# Sheet1.net
KiCad netlist of a schematic drawn in Altium Designer
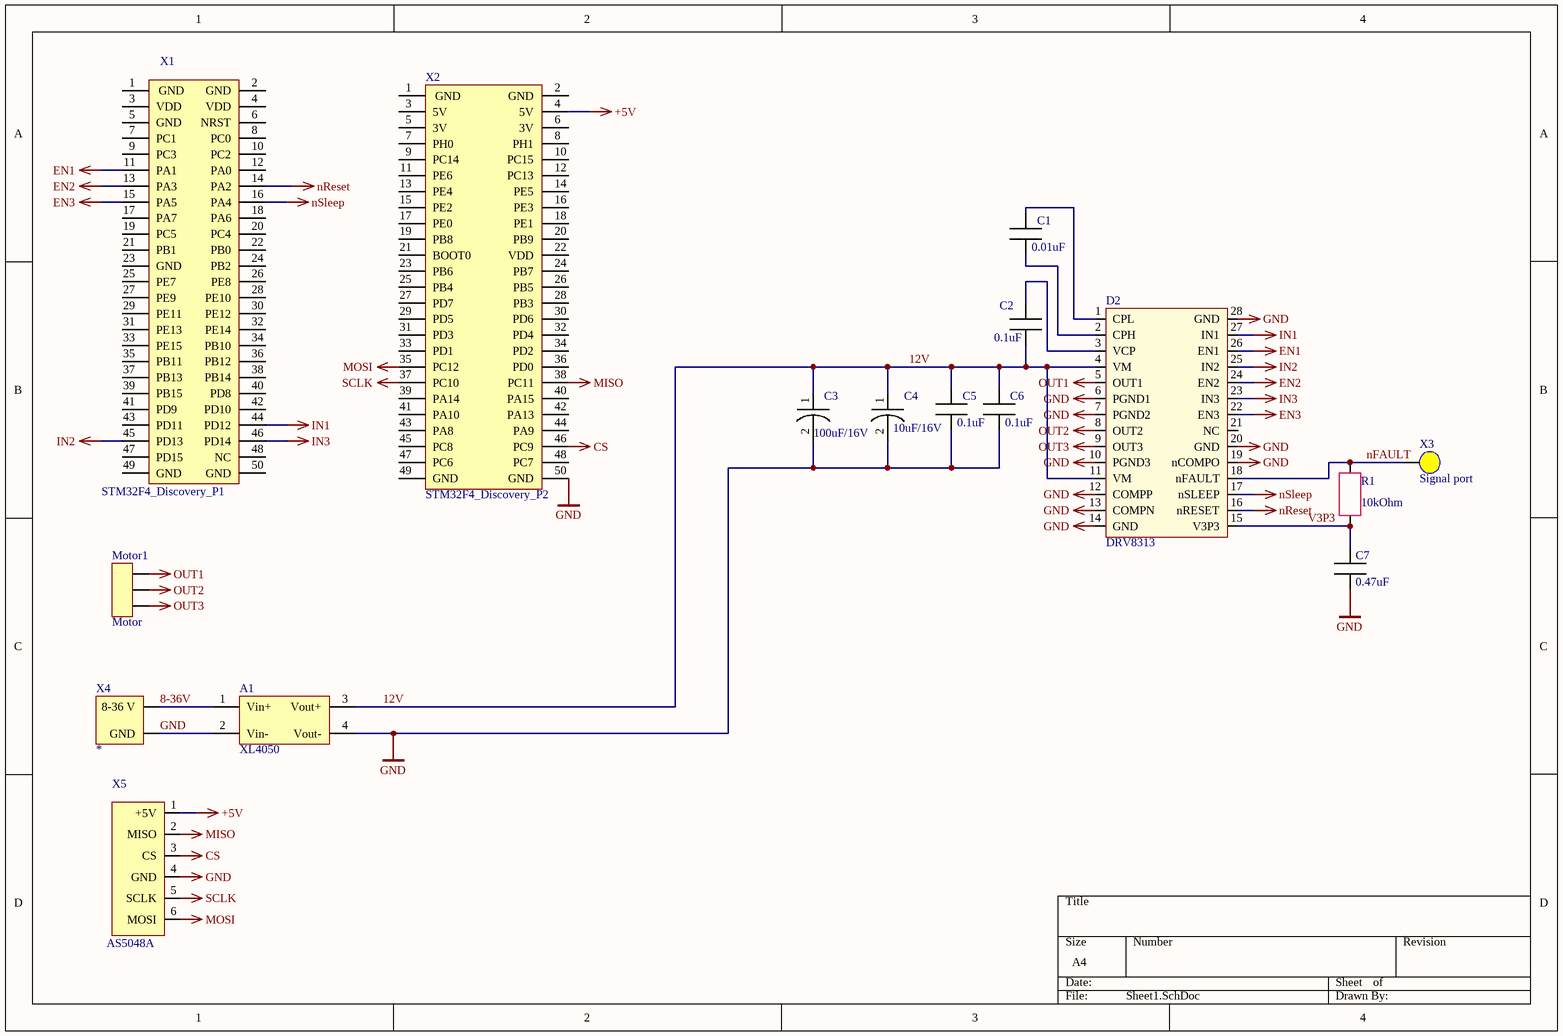
[diagram p0: Sheet1.SchDoc]

(export (version "E")
  (design (tool "Eeschema 10.0.6"))
  (components
    (comp (ref "A1")
      (value "XL4050")
      (footprint "XL4050_PCB")
      (libsource (lib "Schlib1") (part "XL4050_PCB"))
    )
    (comp (ref "C1")
      (value "0.01uF")
      (footprint "Ceramic 1206 - duplicate")
      (libsource (lib "Schlib1") (part "Ceramic capacitor 1206"))
    )
    (comp (ref "C2")
      (value "0.1uF")
      (footprint "Ceramic 1206 - duplicate")
      (libsource (lib "Schlib1") (part "Ceramic capacitor 1206"))
    )
    (comp (ref "C3")
      (value "100uF/16V")
      (footprint "CAP 50-35 5х11")
      (libsource (lib "Schlib1") (part "Elecrolite, К50-35, 100uF/16V"))
    )
    (comp (ref "C4")
      (value "10uF/16V")
      (footprint "CAP 50-35 5х11")
      (libsource (lib "Schlib1") (part "Electrolite, K50-35, 10uF/63V"))
    )
    (comp (ref "C5")
      (value "0.1uF")
      (footprint "Ceramic 1206 - duplicate")
      (libsource (lib "Schlib1") (part "Ceramic capacitor 1206"))
    )
    (comp (ref "C6")
      (value "0.1uF")
      (footprint "Ceramic 1206 - duplicate")
      (libsource (lib "Schlib1") (part "Ceramic capacitor 1206"))
    )
    (comp (ref "C7")
      (value "0.47uF")
      (footprint "Ceramic 1206 - duplicate")
      (libsource (lib "Schlib1") (part "Ceramic capacitor 1206"))
    )
    (comp (ref "D2")
      (value "DRV8313")
      (footprint "PcbLib1:DRV8313 board")
      (libsource (lib "Schlib1") (part "DRV8313"))
    )
    (comp (ref "Motor1")
      (value "Motor")
      (footprint "Fhase out")
      (libsource (lib "Schlib1") (part "Fhase out"))
    )
    (comp (ref "R1")
      (value "10kOhm")
      (footprint "PcbLib1:Resistor 1206")
      (libsource (lib "Schlib1") (part "Resistor"))
    )
    (comp (ref "X1")
      (value "STM32F4_Discovery_P1")
      (footprint "STM32F4Discovery_P")
      (libsource (lib "Schlib1") (part "STM32F4_Discovery_P1"))
    )
    (comp (ref "X2")
      (value "STM32F4_Discovery_P2")
      (footprint "STM32F4Discovery_P")
      (libsource (lib "Schlib1") (part "STM32F4_Discovery_P2"))
    )
    (comp (ref "X3")
      (value "Signal port")
      (footprint "Signal port")
      (libsource (lib "Schlib1") (part "Signal port"))
    )
    (comp (ref "X4") (value "*") (footprint "Power input") (libsource (lib "Schlib1") (part "Power input")))
    (comp (ref "X5")
      (value "AS5048A")
      (footprint "AS5048A_input")
      (libsource (lib "Schlib1") (part "AS5048A_PCB"))
    )
  )
  (nets
    (net (code "1") (name "+5V") (class "Default")
      (node (ref "X2") (pin "4") (pinfunction "5V_4") (pintype "passive"))
      (node (ref "X5") (pin "1") (pinfunction "+5V_1") (pintype "passive"))
    )
    (net (code "2") (name "/8-36V") (class "Default")
      (node (ref "A1") (pin "1") (pinfunction "Vin+_1") (pintype "passive"))
      (node (ref "X4") (pin "1") (pinfunction "8-36_V_1") (pintype "passive"))
    )
    (net (code "3") (name "/12V") (class "Default")
      (node (ref "A1") (pin "3") (pinfunction "Vout+_3") (pintype "passive"))
      (node (ref "C2") (pin "2") (pintype "passive"))
      (node (ref "C3") (pin "1") (pinfunction "+_1") (pintype "passive"))
      (node (ref "C4") (pin "1") (pinfunction "+_1") (pintype "passive"))
      (node (ref "C5") (pin "1") (pintype "passive"))
      (node (ref "C6") (pin "1") (pintype "passive"))
      (node (ref "D2") (pin "11") (pinfunction "VM_11") (pintype "passive"))
      (node (ref "D2") (pin "4") (pinfunction "VM_4") (pintype "passive"))
    )
    (net (code "4") (name "/V3P3") (class "Default")
      (node (ref "C7") (pin "1") (pintype "passive"))
      (node (ref "D2") (pin "15") (pinfunction "V3P3_15") (pintype "passive"))
      (node (ref "R1") (pin "1") (pinfunction "1_1") (pintype "passive"))
    )
    (net (code "5") (name "/nFAULT") (class "Default")
      (node (ref "D2") (pin "18") (pinfunction "nFAULT_18") (pintype "passive"))
      (node (ref "R1") (pin "2") (pinfunction "2_2") (pintype "passive"))
      (node (ref "X3") (pin "1") (pintype "passive"))
    )
    (net (code "6") (name "CS") (class "Default")
      (node (ref "X2") (pin "46") (pinfunction "PC9_46") (pintype "passive"))
      (node (ref "X5") (pin "3") (pinfunction "CS_3") (pintype "passive"))
    )
    (net (code "7") (name "EN1") (class "Default")
      (node (ref "D2") (pin "26") (pinfunction "EN1_26") (pintype "passive"))
      (node (ref "X1") (pin "11") (pinfunction "PA1_11") (pintype "passive"))
    )
    (net (code "8") (name "EN2") (class "Default")
      (node (ref "D2") (pin "24") (pinfunction "EN2_24") (pintype "passive"))
      (node (ref "X1") (pin "13") (pinfunction "PA3_13") (pintype "passive"))
    )
    (net (code "9") (name "EN3") (class "Default")
      (node (ref "D2") (pin "22") (pinfunction "EN3_22") (pintype "passive"))
      (node (ref "X1") (pin "15") (pinfunction "PA5_15") (pintype "passive"))
    )
    (net (code "10") (name "GND") (class "Default")
      (node (ref "A1") (pin "2") (pinfunction "Vin-_2") (pintype "passive"))
      (node (ref "A1") (pin "4") (pinfunction "Vout-_4") (pintype "passive"))
      (node (ref "C3") (pin "2") (pinfunction "-_2") (pintype "passive"))
      (node (ref "C4") (pin "2") (pinfunction "-_2") (pintype "passive"))
      (node (ref "C5") (pin "2") (pintype "passive"))
      (node (ref "C6") (pin "2") (pintype "passive"))
      (node (ref "C7") (pin "2") (pintype "passive"))
      (node (ref "D2") (pin "10") (pinfunction "PGND3_10") (pintype "passive"))
      (node (ref "D2") (pin "12") (pinfunction "COMPP_12") (pintype "passive"))
      (node (ref "D2") (pin "13") (pinfunction "COMPN_13") (pintype "passive"))
      (node (ref "D2") (pin "14") (pinfunction "GND_14") (pintype "passive"))
      (node (ref "D2") (pin "19") (pinfunction "nCOMPO_19") (pintype "passive"))
      (node (ref "D2") (pin "20") (pinfunction "GND_20") (pintype "passive"))
      (node (ref "D2") (pin "28") (pinfunction "GND_28") (pintype "passive"))
      (node (ref "D2") (pin "6") (pinfunction "PGND1_6") (pintype "passive"))
      (node (ref "D2") (pin "7") (pinfunction "PGND2_7") (pintype "passive"))
      (node (ref "X2") (pin "50") (pinfunction "GND_50") (pintype "passive"))
      (node (ref "X4") (pin "2") (pinfunction "GND_2") (pintype "passive"))
      (node (ref "X5") (pin "4") (pinfunction "GND_4") (pintype "passive"))
    )
    (net (code "11") (name "IN1") (class "Default")
      (node (ref "D2") (pin "27") (pinfunction "IN1_27") (pintype "passive"))
      (node (ref "X1") (pin "44") (pinfunction "PD12_44") (pintype "passive"))
    )
    (net (code "12") (name "IN2") (class "Default")
      (node (ref "D2") (pin "25") (pinfunction "IN2_25") (pintype "passive"))
      (node (ref "X1") (pin "45") (pinfunction "PD13_45") (pintype "passive"))
    )
    (net (code "13") (name "IN3") (class "Default")
      (node (ref "D2") (pin "23") (pinfunction "IN3_23") (pintype "passive"))
      (node (ref "X1") (pin "46") (pinfunction "PD14_46") (pintype "passive"))
    )
    (net (code "14") (name "MISO") (class "Default")
      (node (ref "X2") (pin "38") (pinfunction "PC11_38") (pintype "passive"))
      (node (ref "X5") (pin "2") (pinfunction "MISO_2") (pintype "passive"))
    )
    (net (code "15") (name "MOSI") (class "Default")
      (node (ref "X2") (pin "35") (pinfunction "PC12_35") (pintype "passive"))
      (node (ref "X5") (pin "6") (pinfunction "MOSI_6") (pintype "passive"))
    )
    (net (code "16") (name "Net-(D2-CPH)") (class "Default")
      (node (ref "C1") (pin "2") (pintype "passive"))
      (node (ref "D2") (pin "2") (pinfunction "CPH_2") (pintype "passive"))
    )
    (net (code "17") (name "Net-(D2-CPL)") (class "Default")
      (node (ref "C1") (pin "1") (pintype "passive"))
      (node (ref "D2") (pin "1") (pinfunction "CPL_1") (pintype "passive"))
    )
    (net (code "18") (name "Net-(D2-VCP)") (class "Default")
      (node (ref "C2") (pin "1") (pintype "passive"))
      (node (ref "D2") (pin "3") (pinfunction "VCP_3") (pintype "passive"))
    )
    (net (code "19") (name "OUT1") (class "Default")
      (node (ref "D2") (pin "5") (pinfunction "OUT1_5") (pintype "passive"))
      (node (ref "Motor1") (pin "1") (pintype "passive"))
    )
    (net (code "20") (name "OUT2") (class "Default")
      (node (ref "D2") (pin "8") (pinfunction "OUT2_8") (pintype "passive"))
      (node (ref "Motor1") (pin "2") (pintype "passive"))
    )
    (net (code "21") (name "OUT3") (class "Default")
      (node (ref "D2") (pin "9") (pinfunction "OUT3_9") (pintype "passive"))
      (node (ref "Motor1") (pin "3") (pintype "passive"))
    )
    (net (code "22") (name "SCLK") (class "Default")
      (node (ref "X2") (pin "37") (pinfunction "PC10_37") (pintype "passive"))
      (node (ref "X5") (pin "5") (pinfunction "SCLK_5") (pintype "passive"))
    )
    (net (code "23") (name "nReset") (class "Default")
      (node (ref "D2") (pin "16") (pinfunction "nRESET_16") (pintype "passive"))
      (node (ref "X1") (pin "14") (pinfunction "PA2_14") (pintype "passive"))
    )
    (net (code "24") (name "nSleep") (class "Default")
      (node (ref "D2") (pin "17") (pinfunction "nSLEEP_17") (pintype "passive"))
      (node (ref "X1") (pin "16") (pinfunction "PA4_16") (pintype "passive"))
    )
    (net (code "25") (name "unconnected-(D2-NC-Pad21)") (class "Default")
      (node (ref "D2") (pin "21") (pinfunction "NC_21") (pintype "passive"))
    )
    (net (code "26") (name "unconnected-(X1-GND-Pad1)") (class "Default")
      (node (ref "X1") (pin "1") (pinfunction "GND_1") (pintype "passive"))
    )
    (net (code "27") (name "unconnected-(X1-GND-Pad2)") (class "Default")
      (node (ref "X1") (pin "2") (pinfunction "GND_2") (pintype "passive"))
    )
    (net (code "28") (name "unconnected-(X1-GND-Pad5)") (class "Default")
      (node (ref "X1") (pin "5") (pinfunction "GND_5") (pintype "passive"))
    )
    (net (code "29") (name "unconnected-(X1-GND-Pad23)") (class "Default")
      (node (ref "X1") (pin "23") (pinfunction "GND_23") (pintype "passive"))
    )
    (net (code "30") (name "unconnected-(X1-GND-Pad49)") (class "Default")
      (node (ref "X1") (pin "49") (pinfunction "GND_49") (pintype "passive"))
    )
    (net (code "31") (name "unconnected-(X1-GND-Pad50)") (class "Default")
      (node (ref "X1") (pin "50") (pinfunction "GND_50") (pintype "passive"))
    )
    (net (code "32") (name "unconnected-(X1-NC-Pad48)") (class "Default")
      (node (ref "X1") (pin "48") (pinfunction "NC_48") (pintype "passive"))
    )
    (net (code "33") (name "unconnected-(X1-NRST-Pad6)") (class "Default")
      (node (ref "X1") (pin "6") (pinfunction "NRST_6") (pintype "passive"))
    )
    (net (code "34") (name "unconnected-(X1-PA0-Pad12)") (class "Default")
      (node (ref "X1") (pin "12") (pinfunction "PA0_12") (pintype "passive"))
    )
    (net (code "35") (name "unconnected-(X1-PA6-Pad18)") (class "Default")
      (node (ref "X1") (pin "18") (pinfunction "PA6_18") (pintype "passive"))
    )
    (net (code "36") (name "unconnected-(X1-PA7-Pad17)") (class "Default")
      (node (ref "X1") (pin "17") (pinfunction "PA7_17") (pintype "passive"))
    )
    (net (code "37") (name "unconnected-(X1-PB0-Pad22)") (class "Default")
      (node (ref "X1") (pin "22") (pinfunction "PB0_22") (pintype "passive"))
    )
    (net (code "38") (name "unconnected-(X1-PB1-Pad21)") (class "Default")
      (node (ref "X1") (pin "21") (pinfunction "PB1_21") (pintype "passive"))
    )
    (net (code "39") (name "unconnected-(X1-PB2-Pad24)") (class "Default")
      (node (ref "X1") (pin "24") (pinfunction "PB2_24") (pintype "passive"))
    )
    (net (code "40") (name "unconnected-(X1-PB10-Pad34)") (class "Default")
      (node (ref "X1") (pin "34") (pinfunction "PB10_34") (pintype "passive"))
    )
    (net (code "41") (name "unconnected-(X1-PB11-Pad35)") (class "Default")
      (node (ref "X1") (pin "35") (pinfunction "PB11_35") (pintype "passive"))
    )
    (net (code "42") (name "unconnected-(X1-PB12-Pad36)") (class "Default")
      (node (ref "X1") (pin "36") (pinfunction "PB12_36") (pintype "passive"))
    )
    (net (code "43") (name "unconnected-(X1-PB13-Pad37)") (class "Default")
      (node (ref "X1") (pin "37") (pinfunction "PB13_37") (pintype "passive"))
    )
    (net (code "44") (name "unconnected-(X1-PB14-Pad38)") (class "Default")
      (node (ref "X1") (pin "38") (pinfunction "PB14_38") (pintype "passive"))
    )
    (net (code "45") (name "unconnected-(X1-PB15-Pad39)") (class "Default")
      (node (ref "X1") (pin "39") (pinfunction "PB15_39") (pintype "passive"))
    )
    (net (code "46") (name "unconnected-(X1-PC0-Pad8)") (class "Default")
      (node (ref "X1") (pin "8") (pinfunction "PC0_8") (pintype "passive"))
    )
    (net (code "47") (name "unconnected-(X1-PC1-Pad7)") (class "Default")
      (node (ref "X1") (pin "7") (pinfunction "PC1_7") (pintype "passive"))
    )
    (net (code "48") (name "unconnected-(X1-PC2-Pad10)") (class "Default")
      (node (ref "X1") (pin "10") (pinfunction "PC2_10") (pintype "passive"))
    )
    (net (code "49") (name "unconnected-(X1-PC3-Pad9)") (class "Default")
      (node (ref "X1") (pin "9") (pinfunction "PC3_9") (pintype "passive"))
    )
    (net (code "50") (name "unconnected-(X1-PC4-Pad20)") (class "Default")
      (node (ref "X1") (pin "20") (pinfunction "PC4_20") (pintype "passive"))
    )
    (net (code "51") (name "unconnected-(X1-PC5-Pad19)") (class "Default")
      (node (ref "X1") (pin "19") (pinfunction "PC5_19") (pintype "passive"))
    )
    (net (code "52") (name "unconnected-(X1-PD8-Pad40)") (class "Default")
      (node (ref "X1") (pin "40") (pinfunction "PD8_40") (pintype "passive"))
    )
    (net (code "53") (name "unconnected-(X1-PD9-Pad41)") (class "Default")
      (node (ref "X1") (pin "41") (pinfunction "PD9_41") (pintype "passive"))
    )
    (net (code "54") (name "unconnected-(X1-PD10-Pad42)") (class "Default")
      (node (ref "X1") (pin "42") (pinfunction "PD10_42") (pintype "passive"))
    )
    (net (code "55") (name "unconnected-(X1-PD11-Pad43)") (class "Default")
      (node (ref "X1") (pin "43") (pinfunction "PD11_43") (pintype "passive"))
    )
    (net (code "56") (name "unconnected-(X1-PD15-Pad47)") (class "Default")
      (node (ref "X1") (pin "47") (pinfunction "PD15_47") (pintype "passive"))
    )
    (net (code "57") (name "unconnected-(X1-PE7-Pad25)") (class "Default")
      (node (ref "X1") (pin "25") (pinfunction "PE7_25") (pintype "passive"))
    )
    (net (code "58") (name "unconnected-(X1-PE8-Pad26)") (class "Default")
      (node (ref "X1") (pin "26") (pinfunction "PE8_26") (pintype "passive"))
    )
    (net (code "59") (name "unconnected-(X1-PE9-Pad27)") (class "Default")
      (node (ref "X1") (pin "27") (pinfunction "PE9_27") (pintype "passive"))
    )
    (net (code "60") (name "unconnected-(X1-PE10-Pad28)") (class "Default")
      (node (ref "X1") (pin "28") (pinfunction "PE10_28") (pintype "passive"))
    )
    (net (code "61") (name "unconnected-(X1-PE11-Pad29)") (class "Default")
      (node (ref "X1") (pin "29") (pinfunction "PE11_29") (pintype "passive"))
    )
    (net (code "62") (name "unconnected-(X1-PE12-Pad30)") (class "Default")
      (node (ref "X1") (pin "30") (pinfunction "PE12_30") (pintype "passive"))
    )
    (net (code "63") (name "unconnected-(X1-PE13-Pad31)") (class "Default")
      (node (ref "X1") (pin "31") (pinfunction "PE13_31") (pintype "passive"))
    )
    (net (code "64") (name "unconnected-(X1-PE14-Pad32)") (class "Default")
      (node (ref "X1") (pin "32") (pinfunction "PE14_32") (pintype "passive"))
    )
    (net (code "65") (name "unconnected-(X1-PE15-Pad33)") (class "Default")
      (node (ref "X1") (pin "33") (pinfunction "PE15_33") (pintype "passive"))
    )
    (net (code "66") (name "unconnected-(X1-VDD-Pad3)") (class "Default")
      (node (ref "X1") (pin "3") (pinfunction "VDD_3") (pintype "passive"))
    )
    (net (code "67") (name "unconnected-(X1-VDD-Pad4)") (class "Default")
      (node (ref "X1") (pin "4") (pinfunction "VDD_4") (pintype "passive"))
    )
    (net (code "68") (name "unconnected-(X2-3V-Pad5)") (class "Default")
      (node (ref "X2") (pin "5") (pinfunction "3V_5") (pintype "passive"))
    )
    (net (code "69") (name "unconnected-(X2-3V-Pad6)") (class "Default")
      (node (ref "X2") (pin "6") (pinfunction "3V_6") (pintype "passive"))
    )
    (net (code "70") (name "unconnected-(X2-5V-Pad3)") (class "Default")
      (node (ref "X2") (pin "3") (pinfunction "5V_3") (pintype "passive"))
    )
    (net (code "71") (name "unconnected-(X2-BOOT0-Pad21)") (class "Default")
      (node (ref "X2") (pin "21") (pinfunction "BOOT0_21") (pintype "passive"))
    )
    (net (code "72") (name "unconnected-(X2-GND-Pad1)") (class "Default")
      (node (ref "X2") (pin "1") (pinfunction "GND_1") (pintype "passive"))
    )
    (net (code "73") (name "unconnected-(X2-GND-Pad2)") (class "Default")
      (node (ref "X2") (pin "2") (pinfunction "GND_2") (pintype "passive"))
    )
    (net (code "74") (name "unconnected-(X2-GND-Pad49)") (class "Default")
      (node (ref "X2") (pin "49") (pinfunction "GND_49") (pintype "passive"))
    )
    (net (code "75") (name "unconnected-(X2-PA8-Pad43)") (class "Default")
      (node (ref "X2") (pin "43") (pinfunction "PA8_43") (pintype "passive"))
    )
    (net (code "76") (name "unconnected-(X2-PA9-Pad44)") (class "Default")
      (node (ref "X2") (pin "44") (pinfunction "PA9_44") (pintype "passive"))
    )
    (net (code "77") (name "unconnected-(X2-PA10-Pad41)") (class "Default")
      (node (ref "X2") (pin "41") (pinfunction "PA10_41") (pintype "passive"))
    )
    (net (code "78") (name "unconnected-(X2-PA13-Pad42)") (class "Default")
      (node (ref "X2") (pin "42") (pinfunction "PA13_42") (pintype "passive"))
    )
    (net (code "79") (name "unconnected-(X2-PA14-Pad39)") (class "Default")
      (node (ref "X2") (pin "39") (pinfunction "PA14_39") (pintype "passive"))
    )
    (net (code "80") (name "unconnected-(X2-PA15-Pad40)") (class "Default")
      (node (ref "X2") (pin "40") (pinfunction "PA15_40") (pintype "passive"))
    )
    (net (code "81") (name "unconnected-(X2-PB3-Pad28)") (class "Default")
      (node (ref "X2") (pin "28") (pinfunction "PB3_28") (pintype "passive"))
    )
    (net (code "82") (name "unconnected-(X2-PB4-Pad25)") (class "Default")
      (node (ref "X2") (pin "25") (pinfunction "PB4_25") (pintype "passive"))
    )
    (net (code "83") (name "unconnected-(X2-PB5-Pad26)") (class "Default")
      (node (ref "X2") (pin "26") (pinfunction "PB5_26") (pintype "passive"))
    )
    (net (code "84") (name "unconnected-(X2-PB6-Pad23)") (class "Default")
      (node (ref "X2") (pin "23") (pinfunction "PB6_23") (pintype "passive"))
    )
    (net (code "85") (name "unconnected-(X2-PB7-Pad24)") (class "Default")
      (node (ref "X2") (pin "24") (pinfunction "PB7_24") (pintype "passive"))
    )
    (net (code "86") (name "unconnected-(X2-PB8-Pad19)") (class "Default")
      (node (ref "X2") (pin "19") (pinfunction "PB8_19") (pintype "passive"))
    )
    (net (code "87") (name "unconnected-(X2-PB9-Pad20)") (class "Default")
      (node (ref "X2") (pin "20") (pinfunction "PB9_20") (pintype "passive"))
    )
    (net (code "88") (name "unconnected-(X2-PC6-Pad47)") (class "Default")
      (node (ref "X2") (pin "47") (pinfunction "PC6_47") (pintype "passive"))
    )
    (net (code "89") (name "unconnected-(X2-PC7-Pad48)") (class "Default")
      (node (ref "X2") (pin "48") (pinfunction "PC7_48") (pintype "passive"))
    )
    (net (code "90") (name "unconnected-(X2-PC8-Pad45)") (class "Default")
      (node (ref "X2") (pin "45") (pinfunction "PC8_45") (pintype "passive"))
    )
    (net (code "91") (name "unconnected-(X2-PC13-Pad12)") (class "Default")
      (node (ref "X2") (pin "12") (pinfunction "PC13_12") (pintype "passive"))
    )
    (net (code "92") (name "unconnected-(X2-PC14-Pad9)") (class "Default")
      (node (ref "X2") (pin "9") (pinfunction "PC14_9") (pintype "passive"))
    )
    (net (code "93") (name "unconnected-(X2-PC15-Pad10)") (class "Default")
      (node (ref "X2") (pin "10") (pinfunction "PC15_10") (pintype "passive"))
    )
    (net (code "94") (name "unconnected-(X2-PD0-Pad36)") (class "Default")
      (node (ref "X2") (pin "36") (pinfunction "PD0_36") (pintype "passive"))
    )
    (net (code "95") (name "unconnected-(X2-PD1-Pad33)") (class "Default")
      (node (ref "X2") (pin "33") (pinfunction "PD1_33") (pintype "passive"))
    )
    (net (code "96") (name "unconnected-(X2-PD2-Pad34)") (class "Default")
      (node (ref "X2") (pin "34") (pinfunction "PD2_34") (pintype "passive"))
    )
    (net (code "97") (name "unconnected-(X2-PD3-Pad31)") (class "Default")
      (node (ref "X2") (pin "31") (pinfunction "PD3_31") (pintype "passive"))
    )
    (net (code "98") (name "unconnected-(X2-PD4-Pad32)") (class "Default")
      (node (ref "X2") (pin "32") (pinfunction "PD4_32") (pintype "passive"))
    )
    (net (code "99") (name "unconnected-(X2-PD5-Pad29)") (class "Default")
      (node (ref "X2") (pin "29") (pinfunction "PD5_29") (pintype "passive"))
    )
    (net (code "100") (name "unconnected-(X2-PD6-Pad30)") (class "Default")
      (node (ref "X2") (pin "30") (pinfunction "PD6_30") (pintype "passive"))
    )
    (net (code "101") (name "unconnected-(X2-PD7-Pad27)") (class "Default")
      (node (ref "X2") (pin "27") (pinfunction "PD7_27") (pintype "passive"))
    )
    (net (code "102") (name "unconnected-(X2-PE0-Pad17)") (class "Default")
      (node (ref "X2") (pin "17") (pinfunction "PE0_17") (pintype "passive"))
    )
    (net (code "103") (name "unconnected-(X2-PE1-Pad18)") (class "Default")
      (node (ref "X2") (pin "18") (pinfunction "PE1_18") (pintype "passive"))
    )
    (net (code "104") (name "unconnected-(X2-PE2-Pad15)") (class "Default")
      (node (ref "X2") (pin "15") (pinfunction "PE2_15") (pintype "passive"))
    )
    (net (code "105") (name "unconnected-(X2-PE3-Pad16)") (class "Default")
      (node (ref "X2") (pin "16") (pinfunction "PE3_16") (pintype "passive"))
    )
    (net (code "106") (name "unconnected-(X2-PE4-Pad13)") (class "Default")
      (node (ref "X2") (pin "13") (pinfunction "PE4_13") (pintype "passive"))
    )
    (net (code "107") (name "unconnected-(X2-PE5-Pad14)") (class "Default")
      (node (ref "X2") (pin "14") (pinfunction "PE5_14") (pintype "passive"))
    )
    (net (code "108") (name "unconnected-(X2-PE6-Pad11)") (class "Default")
      (node (ref "X2") (pin "11") (pinfunction "PE6_11") (pintype "passive"))
    )
    (net (code "109") (name "unconnected-(X2-PH0-Pad7)") (class "Default")
      (node (ref "X2") (pin "7") (pinfunction "PH0_7") (pintype "passive"))
    )
    (net (code "110") (name "unconnected-(X2-PH1-Pad8)") (class "Default")
      (node (ref "X2") (pin "8") (pinfunction "PH1_8") (pintype "passive"))
    )
    (net (code "111") (name "unconnected-(X2-VDD-Pad22)") (class "Default")
      (node (ref "X2") (pin "22") (pinfunction "VDD_22") (pintype "passive"))
    )
  )
)
